# Nixie.net
KiCad netlist of a schematic drawn in Altium Designer
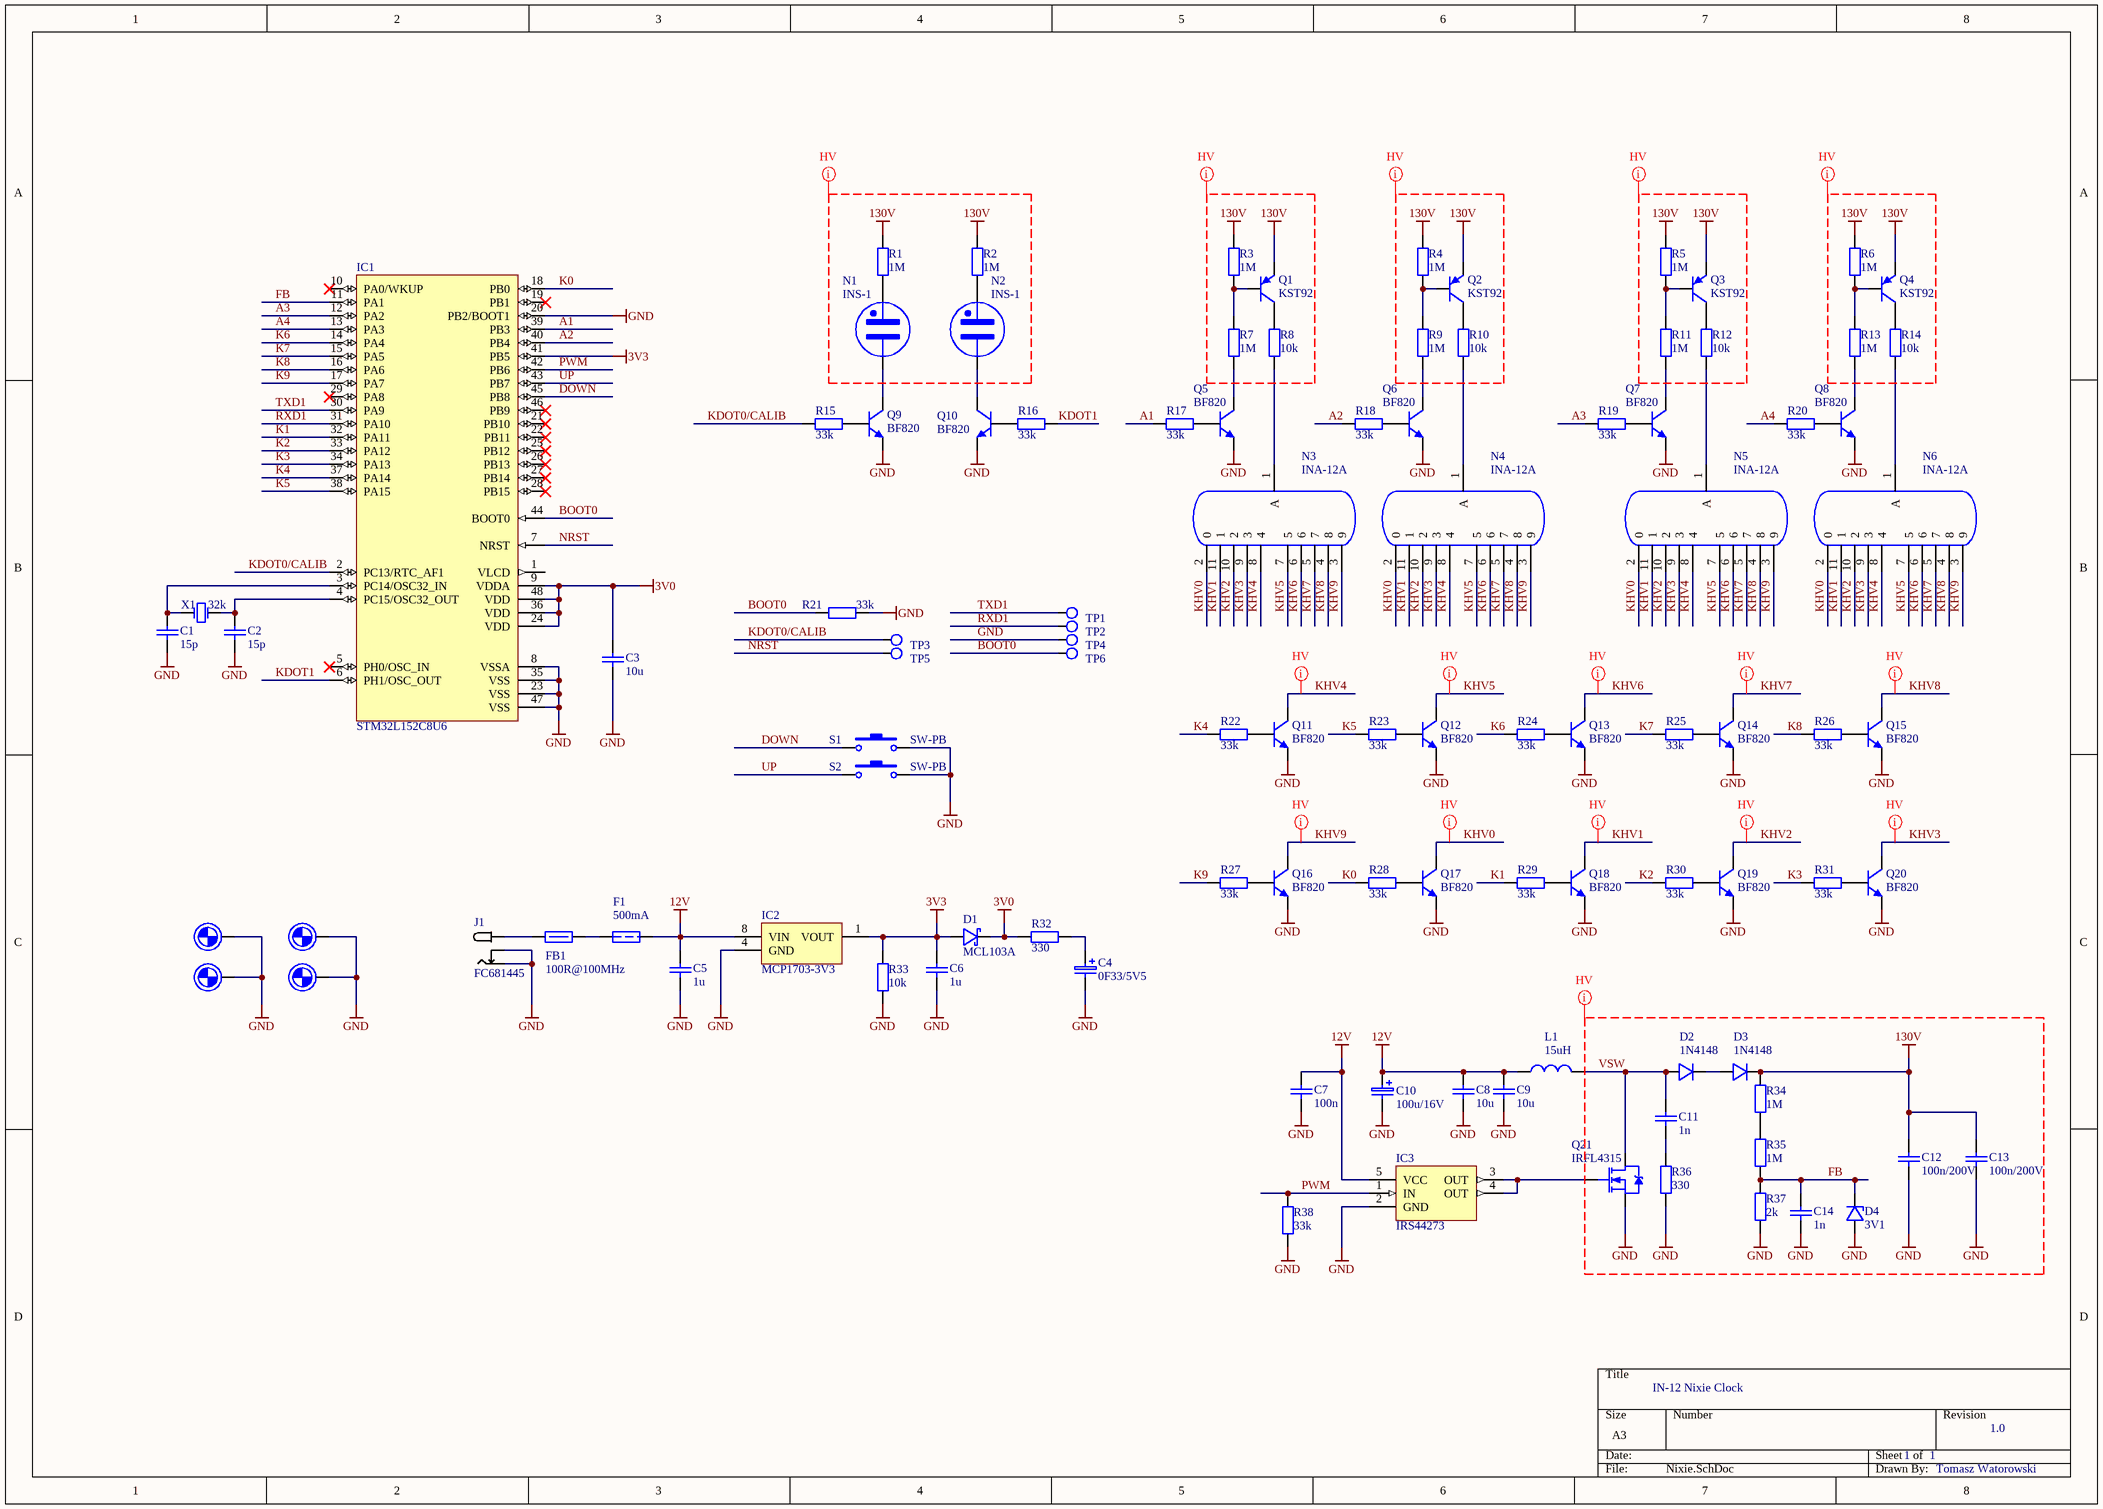
[diagram p0: Nixie.SchDoc]

(export (version "E")
  (design (tool "Eeschema 10.0.6"))
  (components
    (comp (ref "C1")
      (value "15p")
      (footprint "0603_C")
      (description "Capacitor")
      (fields (field (name "PUBLISHER") "Altium Limited"))
      (libsource (lib "MyLib") (part "Capacitor (Non Polar)"))
    )
    (comp (ref "C2")
      (value "15p")
      (footprint "0603_C")
      (description "Capacitor")
      (fields (field (name "PUBLISHER") "Altium Limited"))
      (libsource (lib "MyLib") (part "Capacitor (Non Polar)"))
    )
    (comp (ref "C3")
      (value "10u")
      (footprint "0603_C")
      (description "Capacitor")
      (fields (field (name "PUBLISHER") "Altium Limited"))
      (libsource (lib "MyLib") (part "Capacitor (Non Polar)"))
    )
    (comp (ref "C4")
      (value "0F33/5V5")
      (footprint "CPOL_10x6.5")
      (description "Capacitor")
      (libsource (lib "MyLib") (part "Capacitor (Electrolytic)"))
    )
    (comp (ref "C5")
      (value "1u")
      (footprint "0603_C")
      (description "Capacitor")
      (fields (field (name "PUBLISHER") "Altium Limited"))
      (libsource (lib "MyLib") (part "Capacitor (Non Polar)"))
    )
    (comp (ref "C6")
      (value "1u")
      (footprint "0603_C")
      (description "Capacitor")
      (fields (field (name "PUBLISHER") "Altium Limited"))
      (libsource (lib "MyLib") (part "Capacitor (Non Polar)"))
    )
    (comp (ref "C7")
      (value "100n")
      (footprint "0603_C")
      (description "Capacitor")
      (fields (field (name "PUBLISHER") "Altium Limited"))
      (libsource (lib "MyLib") (part "Capacitor (Non Polar)"))
    )
    (comp (ref "C8")
      (value "10u")
      (footprint "1206_C")
      (description "Capacitor")
      (fields (field (name "PUBLISHER") "Altium Limited"))
      (libsource (lib "MyLib") (part "Capacitor (Non Polar)"))
    )
    (comp (ref "C9")
      (value "10u")
      (footprint "1206_C")
      (description "Capacitor")
      (fields (field (name "PUBLISHER") "Altium Limited"))
      (libsource (lib "MyLib") (part "Capacitor (Non Polar)"))
    )
    (comp (ref "C10")
      (value "100u/16V")
      (footprint "TAJ_C")
      (description "Capacitor")
      (libsource (lib "MyLib") (part "Capacitor (Electrolytic)"))
    )
    (comp (ref "C11")
      (value "1n")
      (footprint "0603_C")
      (description "Capacitor")
      (fields (field (name "PUBLISHER") "Altium Limited"))
      (libsource (lib "MyLib") (part "Capacitor (Non Polar)"))
    )
    (comp (ref "C12")
      (value "100n/200V")
      (footprint "1210_C")
      (description "Capacitor")
      (fields (field (name "PUBLISHER") "Altium Limited"))
      (libsource (lib "MyLib") (part "Capacitor (Non Polar)"))
    )
    (comp (ref "C13")
      (value "100n/200V")
      (footprint "1210_C")
      (description "Capacitor")
      (fields (field (name "PUBLISHER") "Altium Limited"))
      (libsource (lib "MyLib") (part "Capacitor (Non Polar)"))
    )
    (comp (ref "C14")
      (value "1n")
      (footprint "0603_C")
      (description "Capacitor")
      (fields (field (name "PUBLISHER") "Altium Limited"))
      (libsource (lib "MyLib") (part "Capacitor (Non Polar)"))
    )
    (comp (ref "D1")
      (value "MCL103A")
      (footprint "MICROMELF")
      (description "Silicon Diode")
      (fields (field (name "PUBLISHER") "Altium Limited"))
      (libsource (lib "MyLib") (part "Diode Schottky"))
    )
    (comp (ref "D2")
      (value "1N4148")
      (footprint "0805_DSEMI")
      (description "Silicon Diode")
      (fields (field (name "PUBLISHER") "Altium Limited"))
      (libsource (lib "MyLib") (part "Diode"))
    )
    (comp (ref "D3")
      (value "1N4148")
      (footprint "0805_DSEMI")
      (description "Silicon Diode")
      (fields (field (name "PUBLISHER") "Altium Limited"))
      (libsource (lib "MyLib") (part "Diode"))
    )
    (comp (ref "D4")
      (value "3V1")
      (footprint "MICROMELF")
      (description "Silicon Zener Diode")
      (fields (field (name "PUBLISHER") "Altium Limited"))
      (libsource (lib "MyLib") (part "Diode Zener"))
    )
    (comp (ref "F1")
      (value "500mA")
      (footprint "0805_PF")
      (description "Polymer Fuse")
      (fields (field (name "PUBLISHER") "Altium Limited"))
      (libsource (lib "MyLib") (part "Fuse"))
    )
    (comp (ref "FB1")
      (value "100R@100MHz")
      (footprint "0805_FB")
      (description "Ferrite Bead")
      (libsource (lib "MyLib") (part "Ferrite Bead"))
    )
    (comp (ref "IC1")
      (value "STM32L152C8U6")
      (footprint "QFN48")
      (description "Cortex-M3 MCU")
      (libsource (lib "MyLib") (part "STM32L152C6U6"))
    )
    (comp (ref "IC2")
      (value "MCP1703-3V3")
      (footprint "SOT23-3L")
      (description "250 mA, 16V, Low Quiescent Current LDO Regulator")
      (libsource (lib "MyLib") (part "MCP1703"))
    )
    (comp (ref "IC3")
      (value "IRS44273")
      (footprint "SOT23-5AN")
      (description "Single Low-Side Driver IC")
      (libsource (lib "MyLib") (part "IRS44273"))
    )
    (comp (ref "J1")
      (value "FC681445")
      (footprint "FC681445_TH")
      (description "DC Connector")
      (libsource (lib "MyLib") (part "FC681445"))
    )
    (comp (ref "L1")
      (value "15uH")
      (footprint "DLG-0504")
      (description "Inductor")
      (libsource (lib "MyLib") (part "INDUCTOR"))
    )
    (comp (ref "MH1")
      (value "Mouting Hole")
      (footprint "MH_M3")
      (libsource (lib "MyLib") (part "Mouting Hole"))
    )
    (comp (ref "MH2")
      (value "Mouting Hole")
      (footprint "MH_M3")
      (libsource (lib "MyLib") (part "Mouting Hole"))
    )
    (comp (ref "MH3")
      (value "Mouting Hole")
      (footprint "MH_M3")
      (libsource (lib "MyLib") (part "Mouting Hole"))
    )
    (comp (ref "MH4")
      (value "Mouting Hole")
      (footprint "MH_M3")
      (libsource (lib "MyLib") (part "Mouting Hole"))
    )
    (comp (ref "N1")
      (value "INS-1")
      (footprint "INS-1")
      (description "Neon Bulb")
      (libsource (lib "MyLib") (part "INS-1"))
    )
    (comp (ref "N2")
      (value "INS-1")
      (footprint "INS-1")
      (description "Neon Bulb")
      (libsource (lib "MyLib") (part "INS-1"))
    )
    (comp (ref "N3")
      (value "INA-12A")
      (footprint "IN-12")
      (description "Nixie Tube")
      (libsource (lib "MyLib") (part "IN-12A"))
    )
    (comp (ref "N4")
      (value "INA-12A")
      (footprint "IN-12")
      (description "Nixie Tube")
      (libsource (lib "MyLib") (part "IN-12A"))
    )
    (comp (ref "N5")
      (value "INA-12A")
      (footprint "IN-12")
      (description "Nixie Tube")
      (libsource (lib "MyLib") (part "IN-12A"))
    )
    (comp (ref "N6")
      (value "INA-12A")
      (footprint "IN-12")
      (description "Nixie Tube")
      (libsource (lib "MyLib") (part "IN-12A"))
    )
    (comp (ref "Q1") (value "KST92") (footprint "SOT23-3L") (libsource (lib "MyLib") (part "KST92")))
    (comp (ref "Q2") (value "KST92") (footprint "SOT23-3L") (libsource (lib "MyLib") (part "KST92")))
    (comp (ref "Q3") (value "KST92") (footprint "SOT23-3L") (libsource (lib "MyLib") (part "KST92")))
    (comp (ref "Q4") (value "KST92") (footprint "SOT23-3L") (libsource (lib "MyLib") (part "KST92")))
    (comp (ref "Q5")
      (value "BF820")
      (footprint "SOT23-3L")
      (description "NPN high-voltage transistor")
      (libsource (lib "MyLib") (part "BF820"))
    )
    (comp (ref "Q6")
      (value "BF820")
      (footprint "SOT23-3L")
      (description "NPN high-voltage transistor")
      (libsource (lib "MyLib") (part "BF820"))
    )
    (comp (ref "Q7")
      (value "BF820")
      (footprint "SOT23-3L")
      (description "NPN high-voltage transistor")
      (libsource (lib "MyLib") (part "BF820"))
    )
    (comp (ref "Q8")
      (value "BF820")
      (footprint "SOT23-3L")
      (description "NPN high-voltage transistor")
      (libsource (lib "MyLib") (part "BF820"))
    )
    (comp (ref "Q9")
      (value "BF820")
      (footprint "SOT23-3L")
      (description "NPN high-voltage transistor")
      (libsource (lib "MyLib") (part "BF820"))
    )
    (comp (ref "Q10")
      (value "BF820")
      (footprint "SOT23-3L")
      (description "NPN high-voltage transistor")
      (libsource (lib "MyLib") (part "BF820"))
    )
    (comp (ref "Q11")
      (value "BF820")
      (footprint "SOT23-3L")
      (description "NPN high-voltage transistor")
      (libsource (lib "MyLib") (part "BF820"))
    )
    (comp (ref "Q12")
      (value "BF820")
      (footprint "SOT23-3L")
      (description "NPN high-voltage transistor")
      (libsource (lib "MyLib") (part "BF820"))
    )
    (comp (ref "Q13")
      (value "BF820")
      (footprint "SOT23-3L")
      (description "NPN high-voltage transistor")
      (libsource (lib "MyLib") (part "BF820"))
    )
    (comp (ref "Q14")
      (value "BF820")
      (footprint "SOT23-3L")
      (description "NPN high-voltage transistor")
      (libsource (lib "MyLib") (part "BF820"))
    )
    (comp (ref "Q15")
      (value "BF820")
      (footprint "SOT23-3L")
      (description "NPN high-voltage transistor")
      (libsource (lib "MyLib") (part "BF820"))
    )
    (comp (ref "Q16")
      (value "BF820")
      (footprint "SOT23-3L")
      (description "NPN high-voltage transistor")
      (libsource (lib "MyLib") (part "BF820"))
    )
    (comp (ref "Q17")
      (value "BF820")
      (footprint "SOT23-3L")
      (description "NPN high-voltage transistor")
      (libsource (lib "MyLib") (part "BF820"))
    )
    (comp (ref "Q18")
      (value "BF820")
      (footprint "SOT23-3L")
      (description "NPN high-voltage transistor")
      (libsource (lib "MyLib") (part "BF820"))
    )
    (comp (ref "Q19")
      (value "BF820")
      (footprint "SOT23-3L")
      (description "NPN high-voltage transistor")
      (libsource (lib "MyLib") (part "BF820"))
    )
    (comp (ref "Q20")
      (value "BF820")
      (footprint "SOT23-3L")
      (description "NPN high-voltage transistor")
      (libsource (lib "MyLib") (part "BF820"))
    )
    (comp (ref "Q21")
      (value "IRFL4315")
      (footprint "SOT-223_Connected")
      (description "HEXFET Power MOSFET")
      (libsource (lib "MyLib") (part "IRFL4315"))
    )
    (comp (ref "R1")
      (value "1M")
      (footprint "0805_R")
      (description "Resistor")
      (fields (field (name "PUBLISHER") "Altium Limited"))
      (libsource (lib "") (part "Resistor_2"))
    )
    (comp (ref "R2")
      (value "1M")
      (footprint "0805_R")
      (description "Resistor")
      (fields (field (name "PUBLISHER") "Altium Limited"))
      (libsource (lib "") (part "Resistor_3"))
    )
    (comp (ref "R3")
      (value "1M")
      (footprint "0805_R")
      (description "Resistor")
      (fields (field (name "PUBLISHER") "Altium Limited"))
      (libsource (lib "MyLib") (part "Resistor"))
    )
    (comp (ref "R4")
      (value "1M")
      (footprint "0805_R")
      (description "Resistor")
      (fields (field (name "PUBLISHER") "Altium Limited"))
      (libsource (lib "MyLib") (part "Resistor"))
    )
    (comp (ref "R5")
      (value "1M")
      (footprint "0805_R")
      (description "Resistor")
      (fields (field (name "PUBLISHER") "Altium Limited"))
      (libsource (lib "MyLib") (part "Resistor"))
    )
    (comp (ref "R6")
      (value "1M")
      (footprint "0805_R")
      (description "Resistor")
      (fields (field (name "PUBLISHER") "Altium Limited"))
      (libsource (lib "MyLib") (part "Resistor"))
    )
    (comp (ref "R7")
      (value "1M")
      (footprint "0805_R")
      (description "Resistor")
      (fields (field (name "PUBLISHER") "Altium Limited"))
      (libsource (lib "MyLib") (part "Resistor"))
    )
    (comp (ref "R8")
      (value "10k")
      (footprint "0805_R")
      (description "Resistor")
      (fields (field (name "PUBLISHER") "Altium Limited"))
      (libsource (lib "") (part "Resistor_2"))
    )
    (comp (ref "R9")
      (value "1M")
      (footprint "0805_R")
      (description "Resistor")
      (fields (field (name "PUBLISHER") "Altium Limited"))
      (libsource (lib "MyLib") (part "Resistor"))
    )
    (comp (ref "R10")
      (value "10k")
      (footprint "0805_R")
      (description "Resistor")
      (fields (field (name "PUBLISHER") "Altium Limited"))
      (libsource (lib "") (part "Resistor_2"))
    )
    (comp (ref "R11")
      (value "1M")
      (footprint "0805_R")
      (description "Resistor")
      (fields (field (name "PUBLISHER") "Altium Limited"))
      (libsource (lib "MyLib") (part "Resistor"))
    )
    (comp (ref "R12")
      (value "10k")
      (footprint "0805_R")
      (description "Resistor")
      (fields (field (name "PUBLISHER") "Altium Limited"))
      (libsource (lib "") (part "Resistor_2"))
    )
    (comp (ref "R13")
      (value "1M")
      (footprint "0805_R")
      (description "Resistor")
      (fields (field (name "PUBLISHER") "Altium Limited"))
      (libsource (lib "MyLib") (part "Resistor"))
    )
    (comp (ref "R14")
      (value "10k")
      (footprint "0805_R")
      (description "Resistor")
      (fields (field (name "PUBLISHER") "Altium Limited"))
      (libsource (lib "") (part "Resistor_2"))
    )
    (comp (ref "R15")
      (value "33k")
      (footprint "0603_R")
      (description "Resistor")
      (fields (field (name "PUBLISHER") "Altium Limited"))
      (libsource (lib "") (part "Resistor_1"))
    )
    (comp (ref "R16")
      (value "33k")
      (footprint "0603_R")
      (description "Resistor")
      (fields (field (name "PUBLISHER") "Altium Limited"))
      (libsource (lib "") (part "Resistor_2"))
    )
    (comp (ref "R17")
      (value "33k")
      (footprint "0603_R")
      (description "Resistor")
      (fields (field (name "PUBLISHER") "Altium Limited"))
      (libsource (lib "") (part "Resistor_1"))
    )
    (comp (ref "R18")
      (value "33k")
      (footprint "0603_R")
      (description "Resistor")
      (fields (field (name "PUBLISHER") "Altium Limited"))
      (libsource (lib "") (part "Resistor_1"))
    )
    (comp (ref "R19")
      (value "33k")
      (footprint "0603_R")
      (description "Resistor")
      (fields (field (name "PUBLISHER") "Altium Limited"))
      (libsource (lib "") (part "Resistor_1"))
    )
    (comp (ref "R20")
      (value "33k")
      (footprint "0603_R")
      (description "Resistor")
      (fields (field (name "PUBLISHER") "Altium Limited"))
      (libsource (lib "") (part "Resistor_1"))
    )
    (comp (ref "R21")
      (value "33k")
      (footprint "0603_R")
      (description "Resistor")
      (fields (field (name "PUBLISHER") "Altium Limited"))
      (libsource (lib "") (part "Resistor_3"))
    )
    (comp (ref "R22")
      (value "33k")
      (footprint "0603_R")
      (description "Resistor")
      (fields (field (name "PUBLISHER") "Altium Limited"))
      (libsource (lib "") (part "Resistor_1"))
    )
    (comp (ref "R23")
      (value "33k")
      (footprint "0603_R")
      (description "Resistor")
      (fields (field (name "PUBLISHER") "Altium Limited"))
      (libsource (lib "") (part "Resistor_1"))
    )
    (comp (ref "R24")
      (value "33k")
      (footprint "0603_R")
      (description "Resistor")
      (fields (field (name "PUBLISHER") "Altium Limited"))
      (libsource (lib "") (part "Resistor_1"))
    )
    (comp (ref "R25")
      (value "33k")
      (footprint "0603_R")
      (description "Resistor")
      (fields (field (name "PUBLISHER") "Altium Limited"))
      (libsource (lib "") (part "Resistor_1"))
    )
    (comp (ref "R26")
      (value "33k")
      (footprint "0603_R")
      (description "Resistor")
      (fields (field (name "PUBLISHER") "Altium Limited"))
      (libsource (lib "") (part "Resistor_1"))
    )
    (comp (ref "R27")
      (value "33k")
      (footprint "0603_R")
      (description "Resistor")
      (fields (field (name "PUBLISHER") "Altium Limited"))
      (libsource (lib "") (part "Resistor_1"))
    )
    (comp (ref "R28")
      (value "33k")
      (footprint "0603_R")
      (description "Resistor")
      (fields (field (name "PUBLISHER") "Altium Limited"))
      (libsource (lib "") (part "Resistor_1"))
    )
    (comp (ref "R29")
      (value "33k")
      (footprint "0603_R")
      (description "Resistor")
      (fields (field (name "PUBLISHER") "Altium Limited"))
      (libsource (lib "") (part "Resistor_1"))
    )
    (comp (ref "R30")
      (value "33k")
      (footprint "0603_R")
      (description "Resistor")
      (fields (field (name "PUBLISHER") "Altium Limited"))
      (libsource (lib "") (part "Resistor_1"))
    )
    (comp (ref "R31")
      (value "33k")
      (footprint "0603_R")
      (description "Resistor")
      (fields (field (name "PUBLISHER") "Altium Limited"))
      (libsource (lib "") (part "Resistor_1"))
    )
    (comp (ref "R32")
      (value "330")
      (footprint "0603_R")
      (description "Resistor")
      (fields (field (name "PUBLISHER") "Altium Limited"))
      (libsource (lib "") (part "Resistor_3"))
    )
    (comp (ref "R33")
      (value "10k")
      (footprint "0603_R")
      (description "Resistor")
      (fields (field (name "PUBLISHER") "Altium Limited"))
      (libsource (lib "") (part "Resistor_2"))
    )
    (comp (ref "R34")
      (value "1M")
      (footprint "0805_R")
      (description "Resistor")
      (fields (field (name "PUBLISHER") "Altium Limited"))
      (libsource (lib "") (part "Resistor_2"))
    )
    (comp (ref "R35")
      (value "1M")
      (footprint "0805_R")
      (description "Resistor")
      (fields (field (name "PUBLISHER") "Altium Limited"))
      (libsource (lib "") (part "Resistor_2"))
    )
    (comp (ref "R36")
      (value "330")
      (footprint "0805_R")
      (description "Resistor")
      (fields (field (name "PUBLISHER") "Altium Limited"))
      (libsource (lib "") (part "Resistor_2"))
    )
    (comp (ref "R37")
      (value "2k")
      (footprint "0603_R")
      (description "Resistor")
      (fields (field (name "PUBLISHER") "Altium Limited"))
      (libsource (lib "MyLib") (part "Resistor"))
    )
    (comp (ref "R38")
      (value "33k")
      (footprint "0603_R")
      (description "Resistor")
      (fields (field (name "PUBLISHER") "Altium Limited"))
      (libsource (lib "MyLib") (part "Resistor"))
    )
    (comp (ref "S1")
      (value "SW-PB")
      (footprint "DTSM32N")
      (description "Switch")
      (fields (field (name "PUBLISHER") "Altium Limited"))
      (libsource (lib "MyLib") (part "SW-PB"))
    )
    (comp (ref "S2")
      (value "SW-PB")
      (footprint "DTSM32N")
      (description "Switch")
      (fields (field (name "PUBLISHER") "Altium Limited"))
      (libsource (lib "MyLib") (part "SW-PB"))
    )
    (comp (ref "TP1") (value "Test Point") (footprint "TP_1_5") (libsource (lib "MyLib") (part "Test Point")))
    (comp (ref "TP2") (value "Test Point") (footprint "TP_1_5") (libsource (lib "MyLib") (part "Test Point")))
    (comp (ref "TP3") (value "Test Point") (footprint "TP_1_5") (libsource (lib "MyLib") (part "Test Point")))
    (comp (ref "TP4") (value "Test Point") (footprint "TP_1_5") (libsource (lib "MyLib") (part "Test Point")))
    (comp (ref "TP5") (value "Test Point") (footprint "TP_1_5") (libsource (lib "MyLib") (part "Test Point")))
    (comp (ref "TP6") (value "Test Point") (footprint "TP_1_5") (libsource (lib "MyLib") (part "Test Point")))
    (comp (ref "X1")
      (value "32k")
      (footprint "CFPX–217")
      (description "Crystal Resonator")
      (libsource (lib "MyLib") (part "Crystal"))
    )
  )
  (nets
    (net (code "1") (name "/A1") (class "Default")
      (node (ref "IC1") (pin "39") (pinfunction "PB3_39") (pintype "bidirectional"))
      (node (ref "R17") (pin "2") (pinfunction "2_2") (pintype "passive"))
    )
    (net (code "2") (name "/A2") (class "Default")
      (node (ref "IC1") (pin "40") (pinfunction "PB4_40") (pintype "bidirectional"))
      (node (ref "R18") (pin "2") (pinfunction "2_2") (pintype "passive"))
    )
    (net (code "3") (name "/A3") (class "Default")
      (node (ref "IC1") (pin "12") (pinfunction "PA2_12") (pintype "bidirectional"))
      (node (ref "R19") (pin "2") (pinfunction "2_2") (pintype "passive"))
    )
    (net (code "4") (name "/A4") (class "Default")
      (node (ref "IC1") (pin "13") (pinfunction "PA3_13") (pintype "bidirectional"))
      (node (ref "R20") (pin "2") (pinfunction "2_2") (pintype "passive"))
    )
    (net (code "5") (name "/BOOT0") (class "Default")
      (node (ref "IC1") (pin "44") (pinfunction "BOOT0_44") (pintype "input"))
      (node (ref "R21") (pin "1") (pinfunction "1_1") (pintype "passive"))
      (node (ref "TP6") (pin "1") (pinfunction "GND_1") (pintype "passive"))
    )
    (net (code "6") (name "/DOWN") (class "Default")
      (node (ref "IC1") (pin "45") (pinfunction "PB8_45") (pintype "bidirectional"))
      (node (ref "S1") (pin "1") (pinfunction "1_1") (pintype "passive"))
    )
    (net (code "7") (name "/FB") (class "Default")
      (node (ref "C14") (pin "2") (pinfunction "2_2") (pintype "passive"))
      (node (ref "D4") (pin "2") (pinfunction "K_2") (pintype "passive"))
      (node (ref "IC1") (pin "11") (pinfunction "PA1_11") (pintype "bidirectional"))
      (node (ref "R35") (pin "1") (pinfunction "1_1") (pintype "passive"))
      (node (ref "R37") (pin "1") (pinfunction "1_1") (pintype "passive"))
    )
    (net (code "8") (name "/K0") (class "Default")
      (node (ref "IC1") (pin "18") (pinfunction "PB0_18") (pintype "bidirectional"))
      (node (ref "R28") (pin "2") (pinfunction "2_2") (pintype "passive"))
    )
    (net (code "9") (name "/K1") (class "Default")
      (node (ref "IC1") (pin "32") (pinfunction "PA11_32") (pintype "bidirectional"))
      (node (ref "R29") (pin "2") (pinfunction "2_2") (pintype "passive"))
    )
    (net (code "10") (name "/K2") (class "Default")
      (node (ref "IC1") (pin "33") (pinfunction "PA12_33") (pintype "bidirectional"))
      (node (ref "R30") (pin "2") (pinfunction "2_2") (pintype "passive"))
    )
    (net (code "11") (name "/K3") (class "Default")
      (node (ref "IC1") (pin "34") (pinfunction "PA13_34") (pintype "bidirectional"))
      (node (ref "R31") (pin "2") (pinfunction "2_2") (pintype "passive"))
    )
    (net (code "12") (name "/K4") (class "Default")
      (node (ref "IC1") (pin "37") (pinfunction "PA14_37") (pintype "bidirectional"))
      (node (ref "R22") (pin "2") (pinfunction "2_2") (pintype "passive"))
    )
    (net (code "13") (name "/K5") (class "Default")
      (node (ref "IC1") (pin "38") (pinfunction "PA15_38") (pintype "bidirectional"))
      (node (ref "R23") (pin "2") (pinfunction "2_2") (pintype "passive"))
    )
    (net (code "14") (name "/K6") (class "Default")
      (node (ref "IC1") (pin "14") (pinfunction "PA4_14") (pintype "bidirectional"))
      (node (ref "R24") (pin "2") (pinfunction "2_2") (pintype "passive"))
    )
    (net (code "15") (name "/K7") (class "Default")
      (node (ref "IC1") (pin "15") (pinfunction "PA5_15") (pintype "bidirectional"))
      (node (ref "R25") (pin "2") (pinfunction "2_2") (pintype "passive"))
    )
    (net (code "16") (name "/K8") (class "Default")
      (node (ref "IC1") (pin "16") (pinfunction "PA6_16") (pintype "bidirectional"))
      (node (ref "R26") (pin "2") (pinfunction "2_2") (pintype "passive"))
    )
    (net (code "17") (name "/K9") (class "Default")
      (node (ref "IC1") (pin "17") (pinfunction "PA7_17") (pintype "bidirectional"))
      (node (ref "R27") (pin "2") (pinfunction "2_2") (pintype "passive"))
    )
    (net (code "18") (name "/KDOT0{slash}CALIB") (class "Default")
      (node (ref "IC1") (pin "2") (pinfunction "PC13/RTC_AF1_2") (pintype "bidirectional"))
      (node (ref "R15") (pin "2") (pinfunction "2_2") (pintype "passive"))
      (node (ref "TP3") (pin "1") (pinfunction "GND_1") (pintype "passive"))
    )
    (net (code "19") (name "/KDOT1") (class "Default")
      (node (ref "IC1") (pin "6") (pinfunction "PH1/OSC_OUT_6") (pintype "bidirectional"))
      (node (ref "R16") (pin "2") (pinfunction "2_2") (pintype "passive"))
    )
    (net (code "20") (name "/KHV0") (class "Default")
      (node (ref "N3") (pin "2") (pinfunction "0_2") (pintype "power_in"))
      (node (ref "N4") (pin "2") (pinfunction "0_2") (pintype "power_in"))
      (node (ref "N5") (pin "2") (pinfunction "0_2") (pintype "power_in"))
      (node (ref "N6") (pin "2") (pinfunction "0_2") (pintype "power_in"))
      (node (ref "Q17") (pin "3") (pinfunction "C_3") (pintype "passive"))
    )
    (net (code "21") (name "/KHV1") (class "Default")
      (node (ref "N3") (pin "11") (pinfunction "1_11") (pintype "power_in"))
      (node (ref "N4") (pin "11") (pinfunction "1_11") (pintype "power_in"))
      (node (ref "N5") (pin "11") (pinfunction "1_11") (pintype "power_in"))
      (node (ref "N6") (pin "11") (pinfunction "1_11") (pintype "power_in"))
      (node (ref "Q18") (pin "3") (pinfunction "C_3") (pintype "passive"))
    )
    (net (code "22") (name "/KHV2") (class "Default")
      (node (ref "N3") (pin "10") (pinfunction "2_10") (pintype "power_in"))
      (node (ref "N4") (pin "10") (pinfunction "2_10") (pintype "power_in"))
      (node (ref "N5") (pin "10") (pinfunction "2_10") (pintype "power_in"))
      (node (ref "N6") (pin "10") (pinfunction "2_10") (pintype "power_in"))
      (node (ref "Q19") (pin "3") (pinfunction "C_3") (pintype "passive"))
    )
    (net (code "23") (name "/KHV3") (class "Default")
      (node (ref "N3") (pin "9") (pinfunction "3_9") (pintype "power_in"))
      (node (ref "N4") (pin "9") (pinfunction "3_9") (pintype "power_in"))
      (node (ref "N5") (pin "9") (pinfunction "3_9") (pintype "power_in"))
      (node (ref "N6") (pin "9") (pinfunction "3_9") (pintype "power_in"))
      (node (ref "Q20") (pin "3") (pinfunction "C_3") (pintype "passive"))
    )
    (net (code "24") (name "/KHV4") (class "Default")
      (node (ref "N3") (pin "8") (pinfunction "4_8") (pintype "power_in"))
      (node (ref "N4") (pin "8") (pinfunction "4_8") (pintype "power_in"))
      (node (ref "N5") (pin "8") (pinfunction "4_8") (pintype "power_in"))
      (node (ref "N6") (pin "8") (pinfunction "4_8") (pintype "power_in"))
      (node (ref "Q11") (pin "3") (pinfunction "C_3") (pintype "passive"))
    )
    (net (code "25") (name "/KHV5") (class "Default")
      (node (ref "N3") (pin "7") (pinfunction "5_7") (pintype "power_in"))
      (node (ref "N4") (pin "7") (pinfunction "5_7") (pintype "power_in"))
      (node (ref "N5") (pin "7") (pinfunction "5_7") (pintype "power_in"))
      (node (ref "N6") (pin "7") (pinfunction "5_7") (pintype "power_in"))
      (node (ref "Q12") (pin "3") (pinfunction "C_3") (pintype "passive"))
    )
    (net (code "26") (name "/KHV6") (class "Default")
      (node (ref "N3") (pin "6") (pinfunction "6_6") (pintype "power_in"))
      (node (ref "N4") (pin "6") (pinfunction "6_6") (pintype "power_in"))
      (node (ref "N5") (pin "6") (pinfunction "6_6") (pintype "power_in"))
      (node (ref "N6") (pin "6") (pinfunction "6_6") (pintype "power_in"))
      (node (ref "Q13") (pin "3") (pinfunction "C_3") (pintype "passive"))
    )
    (net (code "27") (name "/KHV7") (class "Default")
      (node (ref "N3") (pin "5") (pinfunction "7_5") (pintype "power_in"))
      (node (ref "N4") (pin "5") (pinfunction "7_5") (pintype "power_in"))
      (node (ref "N5") (pin "5") (pinfunction "7_5") (pintype "power_in"))
      (node (ref "N6") (pin "5") (pinfunction "7_5") (pintype "power_in"))
      (node (ref "Q14") (pin "3") (pinfunction "C_3") (pintype "passive"))
    )
    (net (code "28") (name "/KHV8") (class "Default")
      (node (ref "N3") (pin "4") (pinfunction "8_4") (pintype "power_in"))
      (node (ref "N4") (pin "4") (pinfunction "8_4") (pintype "power_in"))
      (node (ref "N5") (pin "4") (pinfunction "8_4") (pintype "power_in"))
      (node (ref "N6") (pin "4") (pinfunction "8_4") (pintype "power_in"))
      (node (ref "Q15") (pin "3") (pinfunction "C_3") (pintype "passive"))
    )
    (net (code "29") (name "/KHV9") (class "Default")
      (node (ref "N3") (pin "3") (pinfunction "9_3") (pintype "power_in"))
      (node (ref "N4") (pin "3") (pinfunction "9_3") (pintype "power_in"))
      (node (ref "N5") (pin "3") (pinfunction "9_3") (pintype "power_in"))
      (node (ref "N6") (pin "3") (pinfunction "9_3") (pintype "power_in"))
      (node (ref "Q16") (pin "3") (pinfunction "C_3") (pintype "passive"))
    )
    (net (code "30") (name "/NRST") (class "Default")
      (node (ref "IC1") (pin "7") (pinfunction "NRST_7") (pintype "input"))
      (node (ref "TP5") (pin "1") (pinfunction "GND_1") (pintype "passive"))
    )
    (net (code "31") (name "/PWM") (class "Default")
      (node (ref "IC1") (pin "42") (pinfunction "PB6_42") (pintype "bidirectional"))
      (node (ref "IC3") (pin "1") (pinfunction "IN_1") (pintype "input"))
      (node (ref "R38") (pin "1") (pinfunction "1_1") (pintype "passive"))
    )
    (net (code "32") (name "/RXD1") (class "Default")
      (node (ref "IC1") (pin "31") (pinfunction "PA10_31") (pintype "bidirectional"))
      (node (ref "TP2") (pin "1") (pinfunction "GND_1") (pintype "passive"))
    )
    (net (code "33") (name "/TXD1") (class "Default")
      (node (ref "IC1") (pin "30") (pinfunction "PA9_30") (pintype "bidirectional"))
      (node (ref "TP1") (pin "1") (pinfunction "GND_1") (pintype "passive"))
    )
    (net (code "34") (name "/UP") (class "Default")
      (node (ref "IC1") (pin "43") (pinfunction "PB7_43") (pintype "bidirectional"))
      (node (ref "S2") (pin "1") (pinfunction "1_1") (pintype "passive"))
    )
    (net (code "35") (name "/VSW") (class "Default")
      (node (ref "C11") (pin "2") (pinfunction "2_2") (pintype "passive"))
      (node (ref "D2") (pin "1") (pinfunction "A_1") (pintype "passive"))
      (node (ref "L1") (pin "2") (pinfunction "2_2") (pintype "passive"))
      (node (ref "Q21") (pin "2") (pinfunction "D_2") (pintype "passive"))
    )
    (net (code "36") (name "3V0") (class "Default")
      (node (ref "C3") (pin "2") (pinfunction "2_2") (pintype "passive"))
      (node (ref "D1") (pin "2") (pinfunction "K_2") (pintype "passive"))
      (node (ref "IC1") (pin "24") (pinfunction "VDD_24") (pintype "power_in"))
      (node (ref "IC1") (pin "36") (pinfunction "VDD_36") (pintype "power_in"))
      (node (ref "IC1") (pin "48") (pinfunction "VDD_48") (pintype "power_in"))
      (node (ref "IC1") (pin "9") (pinfunction "VDDA_9") (pintype "power_in"))
      (node (ref "R32") (pin "1") (pinfunction "1_1") (pintype "passive"))
    )
    (net (code "37") (name "3V3") (class "Default")
      (node (ref "C6") (pin "2") (pinfunction "2_2") (pintype "passive"))
      (node (ref "D1") (pin "1") (pinfunction "A_1") (pintype "passive"))
      (node (ref "IC1") (pin "41") (pinfunction "PB5_41") (pintype "bidirectional"))
      (node (ref "IC2") (pin "1") (pinfunction "VOUT_1") (pintype "power_in"))
      (node (ref "R33") (pin "2") (pinfunction "2_2") (pintype "passive"))
    )
    (net (code "38") (name "12V") (class "Default")
      (node (ref "C10") (pin "1") (pinfunction "1_1") (pintype "passive"))
      (node (ref "C5") (pin "2") (pinfunction "2_2") (pintype "passive"))
      (node (ref "C7") (pin "2") (pinfunction "2_2") (pintype "passive"))
      (node (ref "C8") (pin "2") (pinfunction "2_2") (pintype "passive"))
      (node (ref "C9") (pin "2") (pinfunction "2_2") (pintype "passive"))
      (node (ref "F1") (pin "2") (pinfunction "2_2") (pintype "passive"))
      (node (ref "IC2") (pin "8") (pinfunction "VIN_8") (pintype "power_in"))
      (node (ref "IC3") (pin "5") (pinfunction "VCC_5") (pintype "power_in"))
      (node (ref "L1") (pin "1") (pinfunction "1_1") (pintype "passive"))
    )
    (net (code "39") (name "130V") (class "Default")
      (node (ref "C12") (pin "2") (pinfunction "2_2") (pintype "passive"))
      (node (ref "C13") (pin "2") (pinfunction "2_2") (pintype "passive"))
      (node (ref "D3") (pin "2") (pinfunction "K_2") (pintype "passive"))
      (node (ref "Q1") (pin "2") (pinfunction "E_2") (pintype "passive"))
      (node (ref "Q2") (pin "2") (pinfunction "E_2") (pintype "passive"))
      (node (ref "Q3") (pin "2") (pinfunction "E_2") (pintype "passive"))
      (node (ref "Q4") (pin "2") (pinfunction "E_2") (pintype "passive"))
      (node (ref "R1") (pin "2") (pinfunction "2_2") (pintype "passive"))
      (node (ref "R2") (pin "2") (pinfunction "2_2") (pintype "passive"))
      (node (ref "R3") (pin "1") (pinfunction "1_1") (pintype "passive"))
      (node (ref "R34") (pin "2") (pinfunction "2_2") (pintype "passive"))
      (node (ref "R4") (pin "1") (pinfunction "1_1") (pintype "passive"))
      (node (ref "R5") (pin "1") (pinfunction "1_1") (pintype "passive"))
      (node (ref "R6") (pin "1") (pinfunction "1_1") (pintype "passive"))
    )
    (net (code "40") (name "GND") (class "Default")
      (node (ref "C1") (pin "1") (pinfunction "1_1") (pintype "passive"))
      (node (ref "C10") (pin "2") (pinfunction "2_2") (pintype "passive"))
      (node (ref "C12") (pin "1") (pinfunction "1_1") (pintype "passive"))
      (node (ref "C13") (pin "1") (pinfunction "1_1") (pintype "passive"))
      (node (ref "C14") (pin "1") (pinfunction "1_1") (pintype "passive"))
      (node (ref "C2") (pin "1") (pinfunction "1_1") (pintype "passive"))
      (node (ref "C3") (pin "1") (pinfunction "1_1") (pintype "passive"))
      (node (ref "C4") (pin "2") (pinfunction "2_2") (pintype "passive"))
      (node (ref "C5") (pin "1") (pinfunction "1_1") (pintype "passive"))
      (node (ref "C6") (pin "1") (pinfunction "1_1") (pintype "passive"))
      (node (ref "C7") (pin "1") (pinfunction "1_1") (pintype "passive"))
      (node (ref "C8") (pin "1") (pinfunction "1_1") (pintype "passive"))
      (node (ref "C9") (pin "1") (pinfunction "1_1") (pintype "passive"))
      (node (ref "D4") (pin "1") (pinfunction "A_1") (pintype "passive"))
      (node (ref "IC1") (pin "20") (pinfunction "PB2/BOOT1_20") (pintype "bidirectional"))
      (node (ref "IC1") (pin "23") (pinfunction "VSS_23") (pintype "power_in"))
      (node (ref "IC1") (pin "35") (pinfunction "VSS_35") (pintype "power_in"))
      (node (ref "IC1") (pin "47") (pinfunction "VSS_47") (pintype "power_in"))
      (node (ref "IC1") (pin "8") (pinfunction "VSSA_8") (pintype "power_in"))
      (node (ref "IC2") (pin "4") (pinfunction "GND_4") (pintype "power_in"))
      (node (ref "IC3") (pin "2") (pinfunction "GND_2") (pintype "power_in"))
      (node (ref "J1") (pin "2") (pinfunction "2_2") (pintype "passive"))
      (node (ref "J1") (pin "3") (pinfunction "3_3") (pintype "passive"))
      (node (ref "MH1") (pin "1") (pintype "power_in"))
      (node (ref "MH2") (pin "1") (pintype "power_in"))
      (node (ref "MH3") (pin "1") (pintype "power_in"))
      (node (ref "MH4") (pin "1") (pintype "power_in"))
      (node (ref "Q10") (pin "2") (pinfunction "E_2") (pintype "passive"))
      (node (ref "Q11") (pin "2") (pinfunction "E_2") (pintype "passive"))
      (node (ref "Q12") (pin "2") (pinfunction "E_2") (pintype "passive"))
      (node (ref "Q13") (pin "2") (pinfunction "E_2") (pintype "passive"))
      (node (ref "Q14") (pin "2") (pinfunction "E_2") (pintype "passive"))
      (node (ref "Q15") (pin "2") (pinfunction "E_2") (pintype "passive"))
      (node (ref "Q16") (pin "2") (pinfunction "E_2") (pintype "passive"))
      (node (ref "Q17") (pin "2") (pinfunction "E_2") (pintype "passive"))
      (node (ref "Q18") (pin "2") (pinfunction "E_2") (pintype "passive"))
      (node (ref "Q19") (pin "2") (pinfunction "E_2") (pintype "passive"))
      (node (ref "Q20") (pin "2") (pinfunction "E_2") (pintype "passive"))
      (node (ref "Q21") (pin "3") (pinfunction "S_3") (pintype "passive"))
      (node (ref "Q5") (pin "2") (pinfunction "E_2") (pintype "passive"))
      (node (ref "Q6") (pin "2") (pinfunction "E_2") (pintype "passive"))
      (node (ref "Q7") (pin "2") (pinfunction "E_2") (pintype "passive"))
      (node (ref "Q8") (pin "2") (pinfunction "E_2") (pintype "passive"))
      (node (ref "Q9") (pin "2") (pinfunction "E_2") (pintype "passive"))
      (node (ref "R21") (pin "2") (pinfunction "2_2") (pintype "passive"))
      (node (ref "R33") (pin "1") (pinfunction "1_1") (pintype "passive"))
      (node (ref "R36") (pin "1") (pinfunction "1_1") (pintype "passive"))
      (node (ref "R37") (pin "2") (pinfunction "2_2") (pintype "passive"))
      (node (ref "R38") (pin "2") (pinfunction "2_2") (pintype "passive"))
      (node (ref "S1") (pin "2") (pinfunction "2_2") (pintype "passive"))
      (node (ref "S2") (pin "2") (pinfunction "2_2") (pintype "passive"))
      (node (ref "TP4") (pin "1") (pinfunction "GND_1") (pintype "passive"))
    )
    (net (code "41") (name "Net-(C4-Pad1)") (class "Default")
      (node (ref "C4") (pin "1") (pinfunction "1_1") (pintype "passive"))
      (node (ref "R32") (pin "2") (pinfunction "2_2") (pintype "passive"))
    )
    (net (code "42") (name "Net-(C11-Pad1)") (class "Default")
      (node (ref "C11") (pin "1") (pinfunction "1_1") (pintype "passive"))
      (node (ref "R36") (pin "2") (pinfunction "2_2") (pintype "passive"))
    )
    (net (code "43") (name "Net-(D2-K)") (class "Default")
      (node (ref "D2") (pin "2") (pinfunction "K_2") (pintype "passive"))
      (node (ref "D3") (pin "1") (pinfunction "A_1") (pintype "passive"))
    )
    (net (code "44") (name "Net-(F1-Pad1)") (class "Default")
      (node (ref "F1") (pin "1") (pinfunction "1_1") (pintype "passive"))
      (node (ref "FB1") (pin "2") (pinfunction "2_2") (pintype "passive"))
    )
    (net (code "45") (name "Net-(FB1-Pad1)") (class "Default")
      (node (ref "FB1") (pin "1") (pinfunction "1_1") (pintype "passive"))
      (node (ref "J1") (pin "1") (pinfunction "1_1") (pintype "passive"))
    )
    (net (code "46") (name "Net-(IC1-PC14{slash}OSC32_IN)") (class "Default")
      (node (ref "C1") (pin "2") (pinfunction "2_2") (pintype "passive"))
      (node (ref "IC1") (pin "3") (pinfunction "PC14/OSC32_IN_3") (pintype "bidirectional"))
      (node (ref "X1") (pin "2") (pinfunction "OSC2_2") (pintype "passive"))
    )
    (net (code "47") (name "Net-(IC1-PC15{slash}OSC32_OUT)") (class "Default")
      (node (ref "C2") (pin "2") (pinfunction "2_2") (pintype "passive"))
      (node (ref "IC1") (pin "4") (pinfunction "PC15/OSC32_OUT_4") (pintype "bidirectional"))
      (node (ref "X1") (pin "1") (pinfunction "OSC1_1") (pintype "passive"))
    )
    (net (code "48") (name "Net-(N1-Pad1)") (class "Default")
      (node (ref "N1") (pin "1") (pinfunction "1_1") (pintype "power_in"))
      (node (ref "R1") (pin "1") (pinfunction "1_1") (pintype "passive"))
    )
    (net (code "49") (name "Net-(N2-Pad1)") (class "Default")
      (node (ref "N2") (pin "1") (pinfunction "1_1") (pintype "power_in"))
      (node (ref "R2") (pin "1") (pinfunction "1_1") (pintype "passive"))
    )
    (net (code "50") (name "Net-(N3-A)") (class "Default")
      (node (ref "N3") (pin "1") (pinfunction "A_1") (pintype "power_in"))
      (node (ref "R8") (pin "1") (pinfunction "1_1") (pintype "passive"))
    )
    (net (code "51") (name "Net-(N4-A)") (class "Default")
      (node (ref "N4") (pin "1") (pinfunction "A_1") (pintype "power_in"))
      (node (ref "R10") (pin "1") (pinfunction "1_1") (pintype "passive"))
    )
    (net (code "52") (name "Net-(N5-A)") (class "Default")
      (node (ref "N5") (pin "1") (pinfunction "A_1") (pintype "power_in"))
      (node (ref "R12") (pin "1") (pinfunction "1_1") (pintype "passive"))
    )
    (net (code "53") (name "Net-(N6-A)") (class "Default")
      (node (ref "N6") (pin "1") (pinfunction "A_1") (pintype "power_in"))
      (node (ref "R14") (pin "1") (pinfunction "1_1") (pintype "passive"))
    )
    (net (code "54") (name "Net-(Q1-B)") (class "Default")
      (node (ref "Q1") (pin "1") (pinfunction "B_1") (pintype "passive"))
      (node (ref "R3") (pin "2") (pinfunction "2_2") (pintype "passive"))
      (node (ref "R7") (pin "1") (pinfunction "1_1") (pintype "passive"))
    )
    (net (code "55") (name "Net-(Q1-C)") (class "Default")
      (node (ref "Q1") (pin "3") (pinfunction "C_3") (pintype "passive"))
      (node (ref "R8") (pin "2") (pinfunction "2_2") (pintype "passive"))
    )
    (net (code "56") (name "Net-(Q2-B)") (class "Default")
      (node (ref "Q2") (pin "1") (pinfunction "B_1") (pintype "passive"))
      (node (ref "R4") (pin "2") (pinfunction "2_2") (pintype "passive"))
      (node (ref "R9") (pin "1") (pinfunction "1_1") (pintype "passive"))
    )
    (net (code "57") (name "Net-(Q2-C)") (class "Default")
      (node (ref "Q2") (pin "3") (pinfunction "C_3") (pintype "passive"))
      (node (ref "R10") (pin "2") (pinfunction "2_2") (pintype "passive"))
    )
    (net (code "58") (name "Net-(Q3-B)") (class "Default")
      (node (ref "Q3") (pin "1") (pinfunction "B_1") (pintype "passive"))
      (node (ref "R11") (pin "1") (pinfunction "1_1") (pintype "passive"))
      (node (ref "R5") (pin "2") (pinfunction "2_2") (pintype "passive"))
    )
    (net (code "59") (name "Net-(Q3-C)") (class "Default")
      (node (ref "Q3") (pin "3") (pinfunction "C_3") (pintype "passive"))
      (node (ref "R12") (pin "2") (pinfunction "2_2") (pintype "passive"))
    )
    (net (code "60") (name "Net-(Q4-B)") (class "Default")
      (node (ref "Q4") (pin "1") (pinfunction "B_1") (pintype "passive"))
      (node (ref "R13") (pin "1") (pinfunction "1_1") (pintype "passive"))
      (node (ref "R6") (pin "2") (pinfunction "2_2") (pintype "passive"))
    )
    (net (code "61") (name "Net-(Q4-C)") (class "Default")
      (node (ref "Q4") (pin "3") (pinfunction "C_3") (pintype "passive"))
      (node (ref "R14") (pin "2") (pinfunction "2_2") (pintype "passive"))
    )
    (net (code "62") (name "Net-(Q5-B)") (class "Default")
      (node (ref "Q5") (pin "1") (pinfunction "B_1") (pintype "passive"))
      (node (ref "R17") (pin "1") (pinfunction "1_1") (pintype "passive"))
    )
    (net (code "63") (name "Net-(Q5-C)") (class "Default")
      (node (ref "Q5") (pin "3") (pinfunction "C_3") (pintype "passive"))
      (node (ref "R7") (pin "2") (pinfunction "2_2") (pintype "passive"))
    )
    (net (code "64") (name "Net-(Q6-B)") (class "Default")
      (node (ref "Q6") (pin "1") (pinfunction "B_1") (pintype "passive"))
      (node (ref "R18") (pin "1") (pinfunction "1_1") (pintype "passive"))
    )
    (net (code "65") (name "Net-(Q6-C)") (class "Default")
      (node (ref "Q6") (pin "3") (pinfunction "C_3") (pintype "passive"))
      (node (ref "R9") (pin "2") (pinfunction "2_2") (pintype "passive"))
    )
    (net (code "66") (name "Net-(Q7-B)") (class "Default")
      (node (ref "Q7") (pin "1") (pinfunction "B_1") (pintype "passive"))
      (node (ref "R19") (pin "1") (pinfunction "1_1") (pintype "passive"))
    )
    (net (code "67") (name "Net-(Q7-C)") (class "Default")
      (node (ref "Q7") (pin "3") (pinfunction "C_3") (pintype "passive"))
      (node (ref "R11") (pin "2") (pinfunction "2_2") (pintype "passive"))
    )
    (net (code "68") (name "Net-(Q8-B)") (class "Default")
      (node (ref "Q8") (pin "1") (pinfunction "B_1") (pintype "passive"))
      (node (ref "R20") (pin "1") (pinfunction "1_1") (pintype "passive"))
    )
    (net (code "69") (name "Net-(Q8-C)") (class "Default")
      (node (ref "Q8") (pin "3") (pinfunction "C_3") (pintype "passive"))
      (node (ref "R13") (pin "2") (pinfunction "2_2") (pintype "passive"))
    )
    (net (code "70") (name "Net-(Q9-B)") (class "Default")
      (node (ref "Q9") (pin "1") (pinfunction "B_1") (pintype "passive"))
      (node (ref "R15") (pin "1") (pinfunction "1_1") (pintype "passive"))
    )
    (net (code "71") (name "Net-(Q9-C)") (class "Default")
      (node (ref "N1") (pin "2") (pinfunction "2_2") (pintype "power_in"))
      (node (ref "Q9") (pin "3") (pinfunction "C_3") (pintype "passive"))
    )
    (net (code "72") (name "Net-(Q10-B)") (class "Default")
      (node (ref "Q10") (pin "1") (pinfunction "B_1") (pintype "passive"))
      (node (ref "R16") (pin "1") (pinfunction "1_1") (pintype "passive"))
    )
    (net (code "73") (name "Net-(Q10-C)") (class "Default")
      (node (ref "N2") (pin "2") (pinfunction "2_2") (pintype "power_in"))
      (node (ref "Q10") (pin "3") (pinfunction "C_3") (pintype "passive"))
    )
    (net (code "74") (name "Net-(Q11-B)") (class "Default")
      (node (ref "Q11") (pin "1") (pinfunction "B_1") (pintype "passive"))
      (node (ref "R22") (pin "1") (pinfunction "1_1") (pintype "passive"))
    )
    (net (code "75") (name "Net-(Q12-B)") (class "Default")
      (node (ref "Q12") (pin "1") (pinfunction "B_1") (pintype "passive"))
      (node (ref "R23") (pin "1") (pinfunction "1_1") (pintype "passive"))
    )
    (net (code "76") (name "Net-(Q13-B)") (class "Default")
      (node (ref "Q13") (pin "1") (pinfunction "B_1") (pintype "passive"))
      (node (ref "R24") (pin "1") (pinfunction "1_1") (pintype "passive"))
    )
    (net (code "77") (name "Net-(Q14-B)") (class "Default")
      (node (ref "Q14") (pin "1") (pinfunction "B_1") (pintype "passive"))
      (node (ref "R25") (pin "1") (pinfunction "1_1") (pintype "passive"))
    )
    (net (code "78") (name "Net-(Q15-B)") (class "Default")
      (node (ref "Q15") (pin "1") (pinfunction "B_1") (pintype "passive"))
      (node (ref "R26") (pin "1") (pinfunction "1_1") (pintype "passive"))
    )
    (net (code "79") (name "Net-(Q16-B)") (class "Default")
      (node (ref "Q16") (pin "1") (pinfunction "B_1") (pintype "passive"))
      (node (ref "R27") (pin "1") (pinfunction "1_1") (pintype "passive"))
    )
    (net (code "80") (name "Net-(Q17-B)") (class "Default")
      (node (ref "Q17") (pin "1") (pinfunction "B_1") (pintype "passive"))
      (node (ref "R28") (pin "1") (pinfunction "1_1") (pintype "passive"))
    )
    (net (code "81") (name "Net-(Q18-B)") (class "Default")
      (node (ref "Q18") (pin "1") (pinfunction "B_1") (pintype "passive"))
      (node (ref "R29") (pin "1") (pinfunction "1_1") (pintype "passive"))
    )
    (net (code "82") (name "Net-(Q19-B)") (class "Default")
      (node (ref "Q19") (pin "1") (pinfunction "B_1") (pintype "passive"))
      (node (ref "R30") (pin "1") (pinfunction "1_1") (pintype "passive"))
    )
    (net (code "83") (name "Net-(Q20-B)") (class "Default")
      (node (ref "Q20") (pin "1") (pinfunction "B_1") (pintype "passive"))
      (node (ref "R31") (pin "1") (pinfunction "1_1") (pintype "passive"))
    )
    (net (code "84") (name "Net-(Q21-G)") (class "Default")
      (node (ref "IC3") (pin "3") (pinfunction "OUT_3") (pintype "output"))
      (node (ref "IC3") (pin "4") (pinfunction "OUT_4") (pintype "output"))
      (node (ref "Q21") (pin "1") (pinfunction "G_1") (pintype "passive"))
    )
    (net (code "85") (name "Net-(R34-Pad1)") (class "Default")
      (node (ref "R34") (pin "1") (pinfunction "1_1") (pintype "passive"))
      (node (ref "R35") (pin "2") (pinfunction "2_2") (pintype "passive"))
    )
    (net (code "86") (name "unconnected-(IC1-PA0{slash}WKUP-Pad10)") (class "Default")
      (node (ref "IC1") (pin "10") (pinfunction "PA0/WKUP_10") (pintype "bidirectional+no_connect"))
    )
    (net (code "87") (name "unconnected-(IC1-PA8-Pad29)") (class "Default")
      (node (ref "IC1") (pin "29") (pinfunction "PA8_29") (pintype "bidirectional+no_connect"))
    )
    (net (code "88") (name "unconnected-(IC1-PB1-Pad19)") (class "Default")
      (node (ref "IC1") (pin "19") (pinfunction "PB1_19") (pintype "bidirectional+no_connect"))
    )
    (net (code "89") (name "unconnected-(IC1-PB9-Pad46)") (class "Default")
      (node (ref "IC1") (pin "46") (pinfunction "PB9_46") (pintype "bidirectional+no_connect"))
    )
    (net (code "90") (name "unconnected-(IC1-PB10-Pad21)") (class "Default")
      (node (ref "IC1") (pin "21") (pinfunction "PB10_21") (pintype "bidirectional+no_connect"))
    )
    (net (code "91") (name "unconnected-(IC1-PB11-Pad22)") (class "Default")
      (node (ref "IC1") (pin "22") (pinfunction "PB11_22") (pintype "bidirectional+no_connect"))
    )
    (net (code "92") (name "unconnected-(IC1-PB12-Pad25)") (class "Default")
      (node (ref "IC1") (pin "25") (pinfunction "PB12_25") (pintype "bidirectional+no_connect"))
    )
    (net (code "93") (name "unconnected-(IC1-PB13-Pad26)") (class "Default")
      (node (ref "IC1") (pin "26") (pinfunction "PB13_26") (pintype "bidirectional+no_connect"))
    )
    (net (code "94") (name "unconnected-(IC1-PB14-Pad27)") (class "Default")
      (node (ref "IC1") (pin "27") (pinfunction "PB14_27") (pintype "bidirectional+no_connect"))
    )
    (net (code "95") (name "unconnected-(IC1-PB15-Pad28)") (class "Default")
      (node (ref "IC1") (pin "28") (pinfunction "PB15_28") (pintype "bidirectional+no_connect"))
    )
    (net (code "96") (name "unconnected-(IC1-PH0{slash}OSC_IN-Pad5)") (class "Default")
      (node (ref "IC1") (pin "5") (pinfunction "PH0/OSC_IN_5") (pintype "bidirectional+no_connect"))
    )
    (net (code "97") (name "unconnected-(IC1-VLCD-Pad1)") (class "Default")
      (node (ref "IC1") (pin "1") (pinfunction "VLCD_1") (pintype "output"))
    )
  )
)
